# MCU.net
KiCad netlist of a schematic drawn in Altium Designer
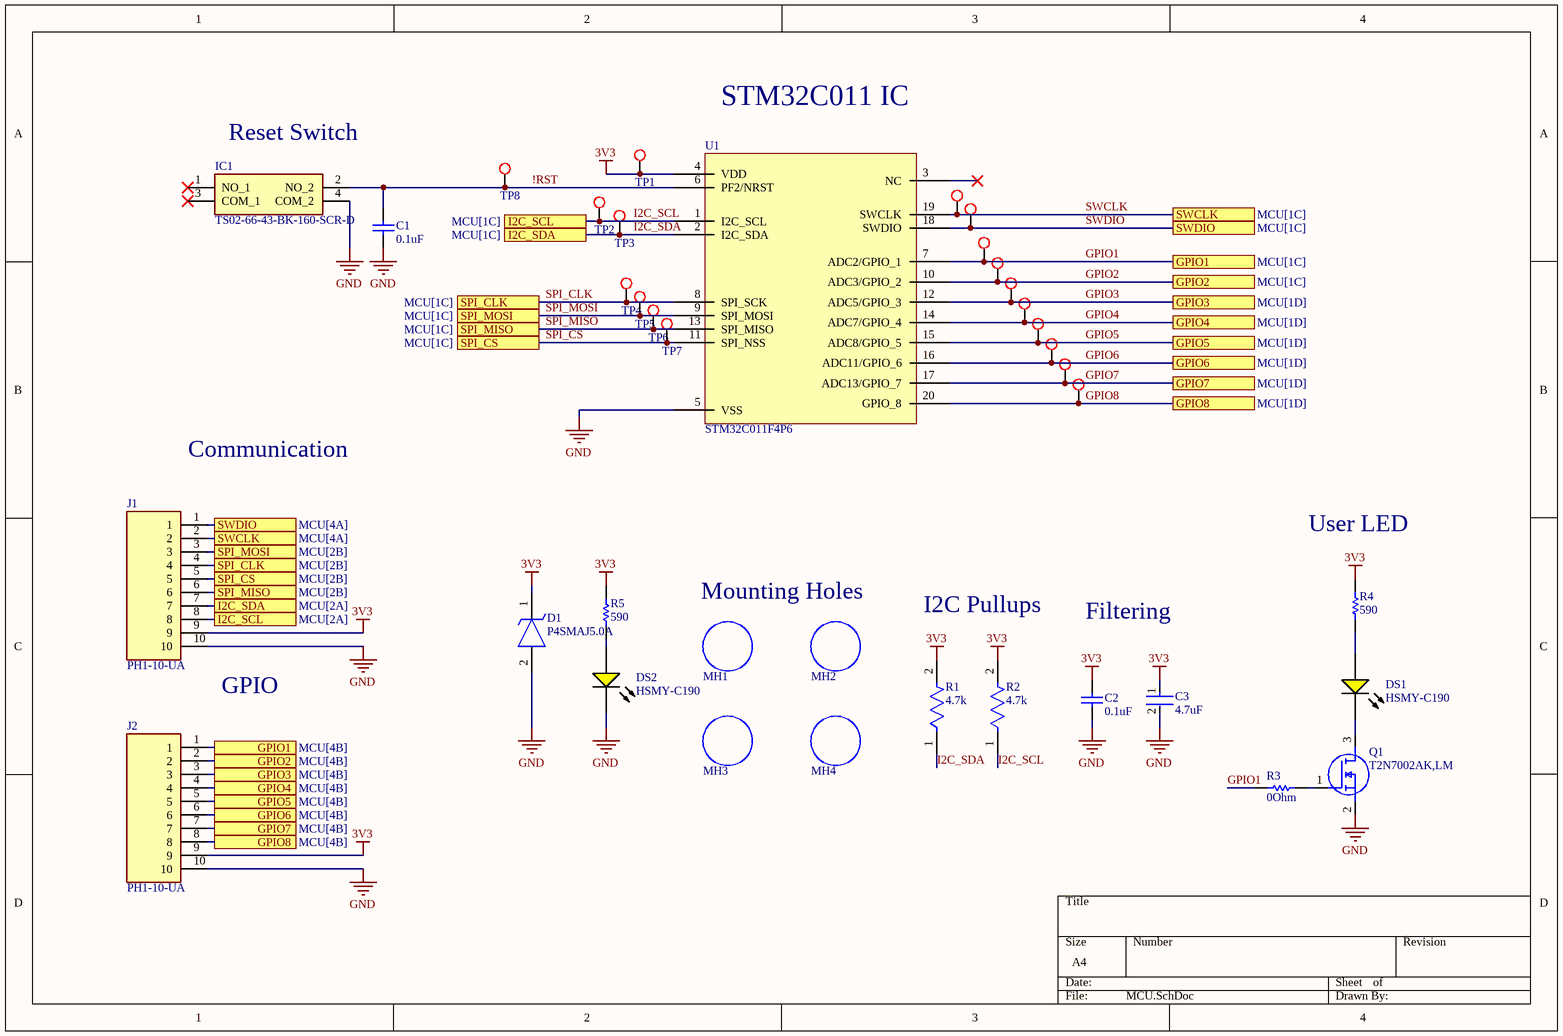
[diagram p0: MCU.SchDoc]

(export (version "E")
  (design (tool "Eeschema 10.0.6"))
  (components
    (comp (ref "C1")
      (value "0.1uF")
      (footprint "CAPC1608X92X38LL15T08")
      (fields (field (name "MANUFACTURER") "Vitramon") (field (name "PART NUMBER") "VJ0603Y104JXJAC"))
      (libsource (lib "Altium Content Vault") (part "CAP"))
    )
    (comp (ref "C2")
      (value "0.1uF")
      (footprint "CAPC1608X92X38LL15T08")
      (fields (field (name "MANUFACTURER") "Vitramon") (field (name "PART NUMBER") "VJ0603Y104JXJAC"))
      (libsource (lib "Altium Content Vault") (part "CAP"))
    )
    (comp (ref "C3")
      (value "4.7uF")
      (footprint "FP-CL10-IPC_A")
      (description "Cap Ceramic 4.7uF 6.3V X6S ±10% Pad SMD 0603 +105°C T/R")
      (fields (field (name "TOLERANCE") "10%"))
      (libsource (lib "Altium Content Vault") (part "b4654b650e69147ec39a6b967a45e02"))
    )
    (comp (ref "D1")
      (value "P4SMAJ5.0A")
      (footprint "SamacSys:DIOM5027X240N")
      (description "TVS Diode (Uni-directional)")
      (libsource (lib "*") (part "P4SMAJ5.0A"))
    )
    (comp (ref "DS1")
      (value "HSMY-C190")
      (footprint "AVAG-HSMX-C190_V")
      (description "LED Uni-Color Yellow, 65 mW, 20 mA, -40 to 85 degC, 2-Pin SMD, RoHS, Tape and Reel")
      (fields (field (name "TOLERANCE") "1%"))
      (libsource (lib "Altium Content Vault") (part "LED-YELLOW-AK-2"))
    )
    (comp (ref "DS2")
      (value "HSMY-C190")
      (footprint "AVAG-HSMX-C190_V")
      (description "LED Uni-Color Yellow, 65 mW, 20 mA, -40 to 85 degC, 2-Pin SMD, RoHS, Tape and Reel")
      (fields (field (name "TOLERANCE") "1%"))
      (libsource (lib "Altium Content Vault") (part "LED-YELLOW-AK-2"))
    )
    (comp (ref "IC1")
      (value "TS02-66-43-BK-160-SCR-D")
      (footprint "SamacSys:TS026643BK160SCRD")
      (description "Integrated Circuit")
      (fields (field (name "MOUSER PART NUMBER") "179-TS026643BK160SCR"))
      (libsource (lib "*") (part "TS02-66-43-BK-160-SCR-D"))
    )
    (comp (ref "J1")
      (value "PH1-10-UA")
      (footprint "SamacSys:HDRV10W64P0X254_1X10_2540X249X886P")
      (description "Connector")
      (fields (field (name "MOUSER PART NUMBER") "737-PH1-10-UA"))
      (libsource (lib "*") (part "PH1-10-UA"))
    )
    (comp (ref "J2")
      (value "PH1-10-UA")
      (footprint "SamacSys:HDRV10W64P0X254_1X10_2540X249X886P")
      (description "Connector")
      (fields (field (name "MOUSER PART NUMBER") "737-PH1-10-UA"))
      (libsource (lib "*") (part "PH1-10-UA"))
    )
    (comp (ref "MH1")
      (value "MH?")
      (footprint "Mounting Hole")
      (libsource (lib "Schlib1") (part "Mounting Hole"))
    )
    (comp (ref "MH2")
      (value "MH?")
      (footprint "Mounting Hole")
      (libsource (lib "Schlib1") (part "Mounting Hole"))
    )
    (comp (ref "MH3")
      (value "MH?")
      (footprint "Mounting Hole")
      (libsource (lib "Schlib1") (part "Mounting Hole"))
    )
    (comp (ref "MH4")
      (value "MH?")
      (footprint "Mounting Hole")
      (libsource (lib "Schlib1") (part "Mounting Hole"))
    )
    (comp (ref "Q1")
      (value "T2N7002AK,LM")
      (footprint "SamacSys:TBAT54CLM")
      (description "MOSFET (N-Channel)")
      (fields (field (name "MOUSER PART NUMBER") "757-T2N7002AKLM"))
      (libsource (lib "*") (part "T2N7002AK,LM"))
    )
    (comp (ref "R1")
      (value "4.7k")
      (footprint "FP-CRCW0603-HPe3-IPC_A")
      (description "RES Thick Film, 4.7kΩ, 5%, 0.33W, 200ppm/°C, 0603")
      (fields (field (name "TOLERANCE") "5%"))
      (libsource (lib "Altium Content Vault") (part "1029c3af85768c4190bb7ad29bc67b5"))
    )
    (comp (ref "R2")
      (value "4.7k")
      (footprint "FP-CRCW0603-HPe3-IPC_A")
      (description "RES Thick Film, 4.7kΩ, 5%, 0.33W, 200ppm/°C, 0603")
      (fields (field (name "TOLERANCE") "5%"))
      (libsource (lib "Altium Content Vault") (part "1029c3af85768c4190bb7ad29bc67b5"))
    )
    (comp (ref "R3")
      (value "0Ohm")
      (footprint "RESC2013X60X35LL10T20")
      (description "Chip Resistor, 0 Ohm, +/- 5%, 125 mW, -55 to 155 degC, 0805 (2012 Metric), RoHS, Tape and Reel")
      (fields (field (name "MANUFACTURER") "Yageo"))
      (libsource (lib "Altium Content Vault") (part "RES-2"))
    )
    (comp (ref "R4")
      (value "590")
      (footprint "RESC1608X55X25ML10T15")
      (fields (field (name "PART NUMBER") "RC0603FR-07590RL") (field (name "MANUFACTURER") "Yageo"))
      (libsource (lib "Altium Content Vault") (part "RES"))
    )
    (comp (ref "R5")
      (value "590")
      (footprint "RESC1608X55X25ML10T15")
      (fields (field (name "PART NUMBER") "RC0603FR-07590RL") (field (name "MANUFACTURER") "Yageo"))
      (libsource (lib "Altium Content Vault") (part "RES"))
    )
    (comp (ref "TP1") (value "TP") (footprint "Testpoint") (libsource (lib "Schlib1") (part "Testpoint")))
    (comp (ref "TP2") (value "TP") (footprint "Testpoint") (libsource (lib "Schlib1") (part "Testpoint")))
    (comp (ref "TP3") (value "TP") (footprint "Testpoint") (libsource (lib "Schlib1") (part "Testpoint")))
    (comp (ref "TP4") (value "TP") (footprint "Testpoint") (libsource (lib "Schlib1") (part "Testpoint")))
    (comp (ref "TP5") (value "TP") (footprint "Testpoint") (libsource (lib "Schlib1") (part "Testpoint")))
    (comp (ref "TP6") (value "TP") (footprint "Testpoint") (libsource (lib "Schlib1") (part "Testpoint")))
    (comp (ref "TP7") (value "TP") (footprint "Testpoint") (libsource (lib "Schlib1") (part "Testpoint")))
    (comp (ref "TP8") (value "TP") (footprint "Testpoint") (libsource (lib "Schlib1") (part "Testpoint")))
    (comp (ref "TP9") (value "TP") (footprint "Testpoint") (libsource (lib "Schlib1") (part "Testpoint")))
    (comp (ref "TP10") (value "TP") (footprint "Testpoint") (libsource (lib "Schlib1") (part "Testpoint")))
    (comp (ref "TP11") (value "TP") (footprint "Testpoint") (libsource (lib "Schlib1") (part "Testpoint")))
    (comp (ref "TP12") (value "TP") (footprint "Testpoint") (libsource (lib "Schlib1") (part "Testpoint")))
    (comp (ref "TP13") (value "TP") (footprint "Testpoint") (libsource (lib "Schlib1") (part "Testpoint")))
    (comp (ref "TP14") (value "TP") (footprint "Testpoint") (libsource (lib "Schlib1") (part "Testpoint")))
    (comp (ref "TP15") (value "TP") (footprint "Testpoint") (libsource (lib "Schlib1") (part "Testpoint")))
    (comp (ref "TP16") (value "TP") (footprint "Testpoint") (libsource (lib "Schlib1") (part "Testpoint")))
    (comp (ref "TP17") (value "TP") (footprint "Testpoint") (libsource (lib "Schlib1") (part "Testpoint")))
    (comp (ref "TP18") (value "TP") (footprint "Testpoint") (libsource (lib "Schlib1") (part "Testpoint")))
    (comp (ref "U1")
      (value "STM32C011F4P6")
      (footprint "TSSOP20")
      (libsource (lib "Schlib1") (part "STM32C011F4P6"))
    )
  )
  (nets
    (net (code "1") (name "/!RST") (class "Default")
      (node (ref "C1") (pin "2") (pinfunction "2_2") (pintype "passive"))
      (node (ref "IC1") (pin "2") (pinfunction "NO_2_2") (pintype "passive"))
      (node (ref "TP8") (pin "0") (pinfunction "0_0") (pintype "passive"))
      (node (ref "U1") (pin "6") (pinfunction "PF2/NRST_6") (pintype "passive"))
    )
    (net (code "2") (name "/GPIO1") (class "Default")
      (node (ref "J2") (pin "1") (pinfunction "1_1") (pintype "passive"))
      (node (ref "R3") (pin "2") (pinfunction "2_2") (pintype "passive"))
      (node (ref "TP11") (pin "0") (pinfunction "0_0") (pintype "passive"))
      (node (ref "U1") (pin "7") (pinfunction "ADC2/GPIO_1_7") (pintype "passive"))
    )
    (net (code "3") (name "/GPIO2") (class "Default")
      (node (ref "J2") (pin "2") (pinfunction "2_2") (pintype "passive"))
      (node (ref "TP12") (pin "0") (pinfunction "0_0") (pintype "passive"))
      (node (ref "U1") (pin "10") (pinfunction "ADC3/GPIO_2_10") (pintype "passive"))
    )
    (net (code "4") (name "/GPIO3") (class "Default")
      (node (ref "J2") (pin "3") (pinfunction "3_3") (pintype "passive"))
      (node (ref "TP13") (pin "0") (pinfunction "0_0") (pintype "passive"))
      (node (ref "U1") (pin "12") (pinfunction "ADC5/GPIO_3_12") (pintype "passive"))
    )
    (net (code "5") (name "/GPIO4") (class "Default")
      (node (ref "J2") (pin "4") (pinfunction "4_4") (pintype "passive"))
      (node (ref "TP14") (pin "0") (pinfunction "0_0") (pintype "passive"))
      (node (ref "U1") (pin "14") (pinfunction "ADC7/GPIO_4_14") (pintype "passive"))
    )
    (net (code "6") (name "/GPIO5") (class "Default")
      (node (ref "J2") (pin "5") (pinfunction "5_5") (pintype "passive"))
      (node (ref "TP15") (pin "0") (pinfunction "0_0") (pintype "passive"))
      (node (ref "U1") (pin "15") (pinfunction "ADC8/GPIO_5_15") (pintype "passive"))
    )
    (net (code "7") (name "/GPIO6") (class "Default")
      (node (ref "J2") (pin "6") (pinfunction "6_6") (pintype "passive"))
      (node (ref "TP16") (pin "0") (pinfunction "0_0") (pintype "passive"))
      (node (ref "U1") (pin "16") (pinfunction "ADC11/GPIO_6_16") (pintype "passive"))
    )
    (net (code "8") (name "/GPIO7") (class "Default")
      (node (ref "J2") (pin "7") (pinfunction "7_7") (pintype "passive"))
      (node (ref "TP17") (pin "0") (pinfunction "0_0") (pintype "passive"))
      (node (ref "U1") (pin "17") (pinfunction "ADC13/GPIO_7_17") (pintype "passive"))
    )
    (net (code "9") (name "/GPIO8") (class "Default")
      (node (ref "J2") (pin "8") (pinfunction "8_8") (pintype "passive"))
      (node (ref "TP18") (pin "0") (pinfunction "0_0") (pintype "passive"))
      (node (ref "U1") (pin "20") (pinfunction "GPIO_8_20") (pintype "passive"))
    )
    (net (code "10") (name "/I2C_SCL") (class "Default")
      (node (ref "J1") (pin "8") (pinfunction "8_8") (pintype "passive"))
      (node (ref "R2") (pin "1") (pinfunction "1_1") (pintype "passive"))
      (node (ref "TP2") (pin "0") (pinfunction "0_0") (pintype "passive"))
      (node (ref "U1") (pin "1") (pinfunction "I2C_SCL_1") (pintype "passive"))
    )
    (net (code "11") (name "/I2C_SDA") (class "Default")
      (node (ref "J1") (pin "7") (pinfunction "7_7") (pintype "passive"))
      (node (ref "R1") (pin "1") (pinfunction "1_1") (pintype "passive"))
      (node (ref "TP3") (pin "0") (pinfunction "0_0") (pintype "passive"))
      (node (ref "U1") (pin "2") (pinfunction "I2C_SDA_2") (pintype "passive"))
    )
    (net (code "12") (name "/SPI_CLK") (class "Default")
      (node (ref "J1") (pin "4") (pinfunction "4_4") (pintype "passive"))
      (node (ref "TP4") (pin "0") (pinfunction "0_0") (pintype "passive"))
      (node (ref "U1") (pin "8") (pinfunction "SPI_SCK_8") (pintype "passive"))
    )
    (net (code "13") (name "/SPI_CS") (class "Default")
      (node (ref "J1") (pin "5") (pinfunction "5_5") (pintype "passive"))
      (node (ref "TP7") (pin "0") (pinfunction "0_0") (pintype "passive"))
      (node (ref "U1") (pin "11") (pinfunction "SPI_NSS_11") (pintype "passive"))
    )
    (net (code "14") (name "/SPI_MISO") (class "Default")
      (node (ref "J1") (pin "6") (pinfunction "6_6") (pintype "passive"))
      (node (ref "TP6") (pin "0") (pinfunction "0_0") (pintype "passive"))
      (node (ref "U1") (pin "13") (pinfunction "SPI_MISO_13") (pintype "passive"))
    )
    (net (code "15") (name "/SPI_MOSI") (class "Default")
      (node (ref "J1") (pin "3") (pinfunction "3_3") (pintype "passive"))
      (node (ref "TP5") (pin "0") (pinfunction "0_0") (pintype "passive"))
      (node (ref "U1") (pin "9") (pinfunction "SPI_MOSI_9") (pintype "passive"))
    )
    (net (code "16") (name "/SWCLK") (class "Default")
      (node (ref "J1") (pin "2") (pinfunction "2_2") (pintype "passive"))
      (node (ref "TP9") (pin "0") (pinfunction "0_0") (pintype "passive"))
      (node (ref "U1") (pin "19") (pinfunction "SWCLK_19") (pintype "passive"))
    )
    (net (code "17") (name "/SWDIO") (class "Default")
      (node (ref "J1") (pin "1") (pinfunction "1_1") (pintype "passive"))
      (node (ref "TP10") (pin "0") (pinfunction "0_0") (pintype "passive"))
      (node (ref "U1") (pin "18") (pinfunction "SWDIO_18") (pintype "passive"))
    )
    (net (code "18") (name "3V3") (class "Default")
      (node (ref "C2") (pin "2") (pinfunction "2_2") (pintype "passive"))
      (node (ref "C3") (pin "1") (pinfunction "1_1") (pintype "passive"))
      (node (ref "D1") (pin "1") (pinfunction "K_1") (pintype "passive"))
      (node (ref "J1") (pin "9") (pinfunction "9_9") (pintype "passive"))
      (node (ref "J2") (pin "9") (pinfunction "9_9") (pintype "passive"))
      (node (ref "R1") (pin "2") (pinfunction "2_2") (pintype "passive"))
      (node (ref "R2") (pin "2") (pinfunction "2_2") (pintype "passive"))
      (node (ref "R4") (pin "2") (pinfunction "2_2") (pintype "passive"))
      (node (ref "R5") (pin "2") (pinfunction "2_2") (pintype "passive"))
      (node (ref "TP1") (pin "0") (pinfunction "0_0") (pintype "passive"))
      (node (ref "U1") (pin "4") (pinfunction "VDD_4") (pintype "passive"))
    )
    (net (code "19") (name "GND") (class "Default")
      (node (ref "C1") (pin "1") (pinfunction "1_1") (pintype "passive"))
      (node (ref "C2") (pin "1") (pinfunction "1_1") (pintype "passive"))
      (node (ref "C3") (pin "2") (pinfunction "2_2") (pintype "passive"))
      (node (ref "D1") (pin "2") (pinfunction "A_2") (pintype "passive"))
      (node (ref "DS2") (pin "2") (pinfunction "K_2") (pintype "passive"))
      (node (ref "IC1") (pin "4") (pinfunction "COM_2_4") (pintype "passive"))
      (node (ref "J1") (pin "10") (pinfunction "10_10") (pintype "passive"))
      (node (ref "J2") (pin "10") (pinfunction "10_10") (pintype "passive"))
      (node (ref "Q1") (pin "2") (pinfunction "S_2") (pintype "passive"))
      (node (ref "U1") (pin "5") (pinfunction "VSS_5") (pintype "passive"))
    )
    (net (code "20") (name "Net-(DS1-A)") (class "Default")
      (node (ref "DS1") (pin "1") (pinfunction "A_1") (pintype "passive"))
      (node (ref "R4") (pin "1") (pinfunction "1_1") (pintype "passive"))
    )
    (net (code "21") (name "Net-(DS1-K)") (class "Default")
      (node (ref "DS1") (pin "2") (pinfunction "K_2") (pintype "passive"))
      (node (ref "Q1") (pin "3") (pinfunction "D_3") (pintype "passive"))
    )
    (net (code "22") (name "Net-(DS2-A)") (class "Default")
      (node (ref "DS2") (pin "1") (pinfunction "A_1") (pintype "passive"))
      (node (ref "R5") (pin "1") (pinfunction "1_1") (pintype "passive"))
    )
    (net (code "23") (name "Net-(Q1-G)") (class "Default")
      (node (ref "Q1") (pin "1") (pinfunction "G_1") (pintype "passive"))
      (node (ref "R3") (pin "1") (pinfunction "1_1") (pintype "passive"))
    )
    (net (code "24") (name "unconnected-(IC1-COM_1-Pad3)") (class "Default")
      (node (ref "IC1") (pin "3") (pinfunction "COM_1_3") (pintype "passive+no_connect"))
    )
    (net (code "25") (name "unconnected-(IC1-NO_1-Pad1)") (class "Default")
      (node (ref "IC1") (pin "1") (pinfunction "NO_1_1") (pintype "passive+no_connect"))
    )
    (net (code "26") (name "unconnected-(U1-NC-Pad3)") (class "Default")
      (node (ref "U1") (pin "3") (pinfunction "NC_3") (pintype "passive+no_connect"))
    )
  )
)
